# MCISO-S08-V00-Peripherals.net
KiCad netlist of a schematic drawn in Altium Designer
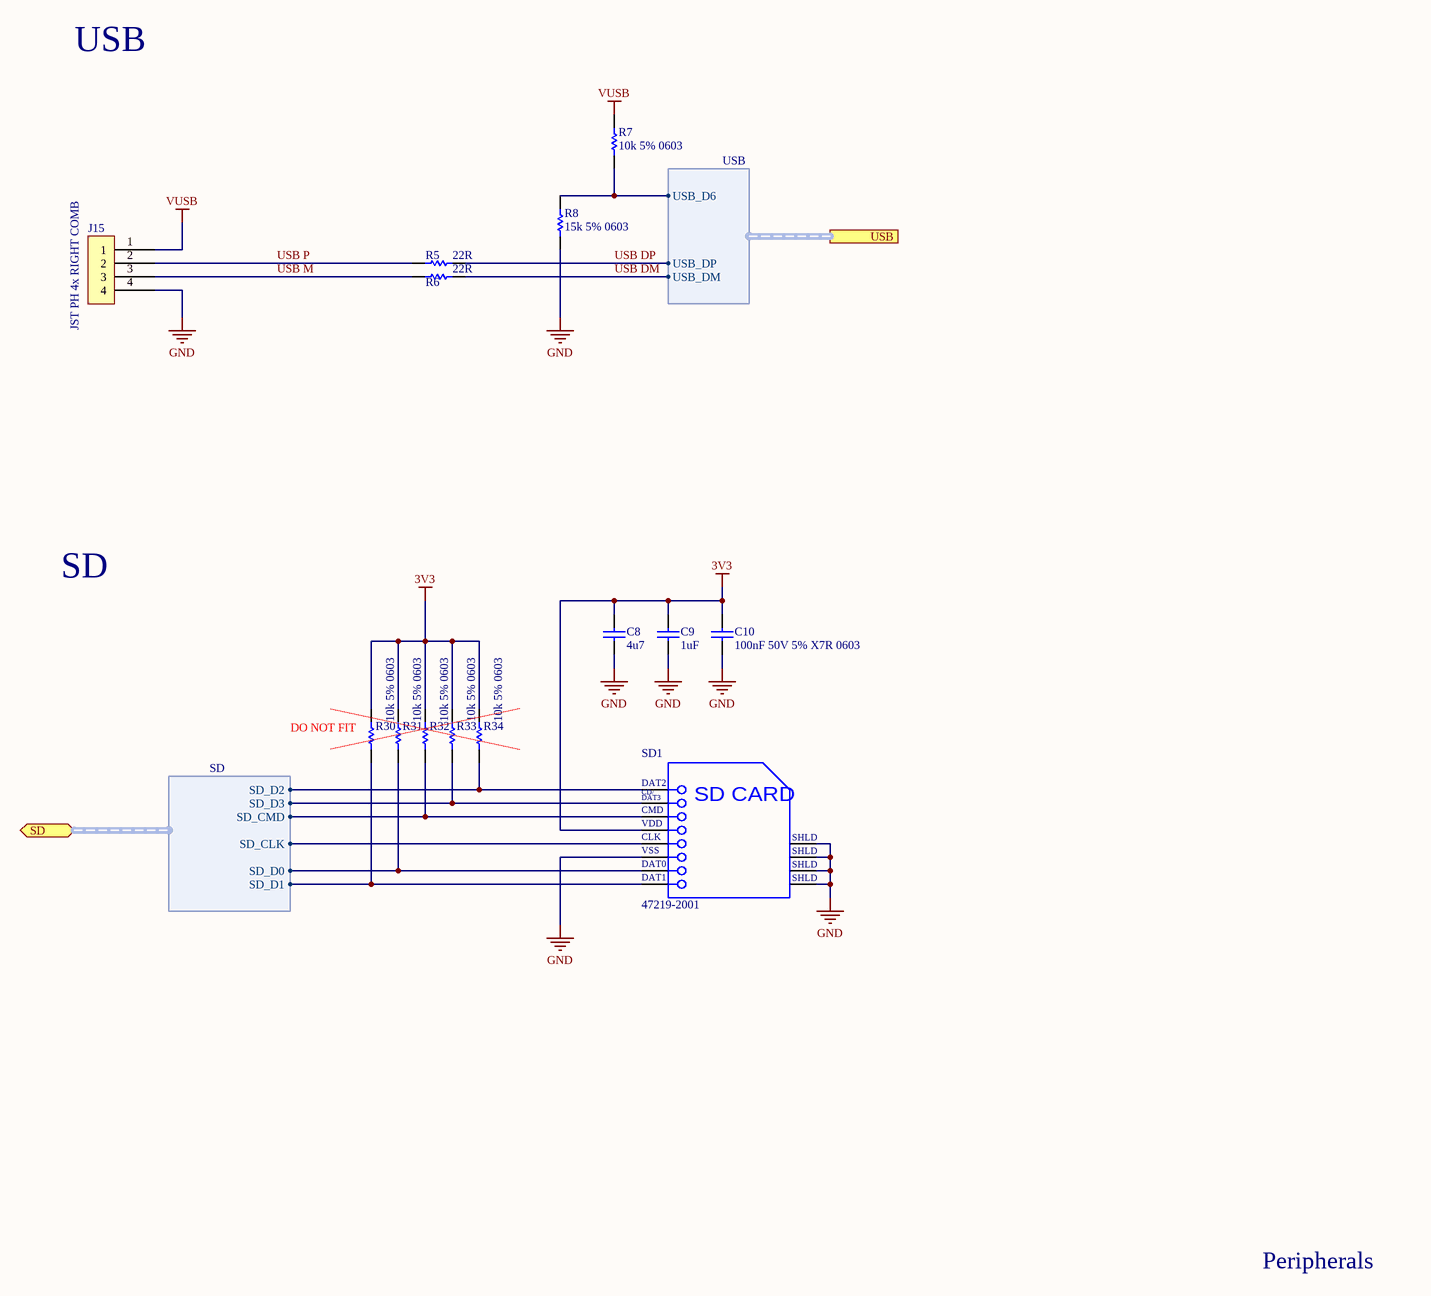
[diagram p0: MCISO-S08-V00-Peripherals.SchDoc]

(export (version "E")
  (design (tool "Eeschema 10.0.6"))
  (components
    (comp (ref "C8")
      (value "4u7")
      (footprint "Cap_Ceramic_0603")
      (description "Capacitor, Ceramic, SMD, 4u7, 50V, 5%, X7R, 0603")
      (libsource (lib "StandardCapacitors") (part "4u7 50V 5% X7R 0603"))
    )
    (comp (ref "C9")
      (value "1uF")
      (footprint "Cap_Ceramic_0603")
      (description "Capacitor, Ceramic, SMD, 1uF, 25V, 5%, X7R, 0603")
      (libsource (lib "StandardCapacitors") (part "1uF 25V 5% X7R 0603"))
    )
    (comp (ref "C10")
      (value "100nF 50V 5% X7R 0603")
      (footprint "Cap_Ceramic_0603")
      (description "Capacitor, Ceramic, SMD, 100nF, 50V, 5%, X7R, 0603")
      (libsource (lib "StandardCapacitors") (part "100nF 50V 5% X7R 0603"))
    )
    (comp (ref "J15")
      (value "JST PH 4x RIGHT COMB")
      (footprint "JST PH 4x RIGHT COMB")
      (libsource (lib "QUTMS-MCISOLibrary") (part "JST PH 4x RIGHT COMB"))
    )
    (comp (ref "R5")
      (value "22R")
      (footprint "Res_ThinFilm_0603")
      (description "Resistor, SMD, 22R, 0.1W, 1%, 0603")
      (libsource (lib "QUTMS-MCISOLibrary") (part "22R 1% 0603"))
    )
    (comp (ref "R6")
      (value "22R")
      (footprint "Res_ThinFilm_0603")
      (description "Resistor, SMD, 22R, 0.1W, 1%, 0603")
      (libsource (lib "QUTMS-MCISOLibrary") (part "22R 1% 0603"))
    )
    (comp (ref "R7")
      (value "10k 5% 0603")
      (footprint "Res_ThinFilm_0603")
      (description "Resistor, SMD, 10k, 0.1W, 5%, 0603")
      (libsource (lib "StandardResistors") (part "10k 5% 0603"))
    )
    (comp (ref "R8")
      (value "15k 5% 0603")
      (footprint "Res_ThinFilm_0603")
      (description "Resistor, SMD, 15k, 0.1W, 5%, 0603")
      (libsource (lib "StandardResistors") (part "15k 5% 0603"))
    )
    (comp (ref "R30")
      (value "10k 5% 0603")
      (footprint "Res_ThinFilm_0603")
      (description "Resistor, SMD, 10k, 0.1W, 5%, 0603")
      (libsource (lib "StandardResistors") (part "10k 5% 0603"))
    )
    (comp (ref "R31")
      (value "10k 5% 0603")
      (footprint "Res_ThinFilm_0603")
      (description "Resistor, SMD, 10k, 0.1W, 5%, 0603")
      (libsource (lib "StandardResistors") (part "10k 5% 0603"))
    )
    (comp (ref "R32")
      (value "10k 5% 0603")
      (footprint "Res_ThinFilm_0603")
      (description "Resistor, SMD, 10k, 0.1W, 5%, 0603")
      (libsource (lib "StandardResistors") (part "10k 5% 0603"))
    )
    (comp (ref "R33")
      (value "10k 5% 0603")
      (footprint "Res_ThinFilm_0603")
      (description "Resistor, SMD, 10k, 0.1W, 5%, 0603")
      (libsource (lib "StandardResistors") (part "10k 5% 0603"))
    )
    (comp (ref "R34")
      (value "10k 5% 0603")
      (footprint "Res_ThinFilm_0603")
      (description "Resistor, SMD, 10k, 0.1W, 5%, 0603")
      (libsource (lib "StandardResistors") (part "10k 5% 0603"))
    )
    (comp (ref "SD1")
      (value "47219-2001")
      (footprint "MOLX-47219-2001-8_V")
      (description "MicroSD Card Connector, Hinge Type, -40 to 85 degC, 8-Pin SMD, RoHS, Tape and Reel")
      (fields (field (name "MANUFACTURER") "Molex"))
      (libsource (lib "Altium Content Vault") (part "CN-SD-8-4S"))
    )
  )
  (nets
    (net (code "3") (name "/SD_CLK") (class "Default")
      (node (ref "SD1") (pin "5") (pinfunction "CLK_5") (pintype "passive"))
    )
    (net (code "4") (name "/SD_CMD") (class "Default")
      (node (ref "R32") (pin "1") (pinfunction "1_1") (pintype "passive"))
      (node (ref "SD1") (pin "3") (pinfunction "CMD_3") (pintype "passive"))
    )
    (net (code "5") (name "/SD_D0") (class "Default")
      (node (ref "R31") (pin "1") (pinfunction "1_1") (pintype "passive"))
      (node (ref "SD1") (pin "7") (pinfunction "DAT0_7") (pintype "passive"))
    )
    (net (code "6") (name "/SD_D1") (class "Default")
      (node (ref "R30") (pin "1") (pinfunction "1_1") (pintype "passive"))
      (node (ref "SD1") (pin "8") (pinfunction "DAT1_8") (pintype "passive"))
    )
    (net (code "7") (name "/SD_D2") (class "Default")
      (node (ref "R34") (pin "1") (pinfunction "1_1") (pintype "passive"))
      (node (ref "SD1") (pin "1") (pinfunction "DAT2_1") (pintype "passive"))
    )
    (net (code "8") (name "/SD_D3") (class "Default")
      (node (ref "R33") (pin "1") (pinfunction "1_1") (pintype "passive"))
      (node (ref "SD1") (pin "2") (pinfunction "CD/DAT3_2") (pintype "passive"))
    )
    (net (code "9") (name "/USB DM") (class "Default")
      (node (ref "R6") (pin "2") (pinfunction "2_2") (pintype "passive"))
    )
    (net (code "10") (name "/USB DP") (class "Default")
      (node (ref "R5") (pin "2") (pinfunction "2_2") (pintype "passive"))
    )
    (net (code "11") (name "/USB M") (class "Default")
      (node (ref "J15") (pin "3") (pinfunction "3_3") (pintype "passive"))
      (node (ref "R6") (pin "1") (pinfunction "1_1") (pintype "passive"))
    )
    (net (code "12") (name "/USB P") (class "Default")
      (node (ref "J15") (pin "2") (pinfunction "2_2") (pintype "passive"))
      (node (ref "R5") (pin "1") (pinfunction "1_1") (pintype "passive"))
    )
    (net (code "13") (name "/USB_D6") (class "Default")
      (node (ref "R7") (pin "1") (pinfunction "1_1") (pintype "passive"))
      (node (ref "R8") (pin "2") (pinfunction "2_2") (pintype "passive"))
    )
    (net (code "16") (name "3V3") (class "Default")
      (node (ref "C10") (pin "2") (pinfunction "2_2") (pintype "passive"))
      (node (ref "C8") (pin "2") (pinfunction "2_2") (pintype "passive"))
      (node (ref "C9") (pin "2") (pinfunction "2_2") (pintype "passive"))
      (node (ref "R30") (pin "2") (pinfunction "2_2") (pintype "passive"))
      (node (ref "R31") (pin "2") (pinfunction "2_2") (pintype "passive"))
      (node (ref "R32") (pin "2") (pinfunction "2_2") (pintype "passive"))
      (node (ref "R33") (pin "2") (pinfunction "2_2") (pintype "passive"))
      (node (ref "R34") (pin "2") (pinfunction "2_2") (pintype "passive"))
      (node (ref "SD1") (pin "4") (pinfunction "VDD_4") (pintype "passive"))
    )
    (net (code "17") (name "GND") (class "Default")
      (node (ref "C10") (pin "1") (pinfunction "1_1") (pintype "passive"))
      (node (ref "C8") (pin "1") (pinfunction "1_1") (pintype "passive"))
      (node (ref "C9") (pin "1") (pinfunction "1_1") (pintype "passive"))
      (node (ref "J15") (pin "4") (pinfunction "4_4") (pintype "passive"))
      (node (ref "R8") (pin "1") (pinfunction "1_1") (pintype "passive"))
      (node (ref "SD1") (pin "10") (pinfunction "SHLD_10") (pintype "passive"))
      (node (ref "SD1") (pin "11") (pinfunction "SHLD_11") (pintype "passive"))
      (node (ref "SD1") (pin "12") (pinfunction "SHLD_12") (pintype "passive"))
      (node (ref "SD1") (pin "6") (pinfunction "VSS_6") (pintype "passive"))
      (node (ref "SD1") (pin "9") (pinfunction "SHLD_9") (pintype "passive"))
    )
    (net (code "18") (name "VUSB") (class "Default")
      (node (ref "J15") (pin "1") (pinfunction "1_1") (pintype "passive"))
      (node (ref "R7") (pin "2") (pinfunction "2_2") (pintype "passive"))
    )
  )
)
